# 05_LEDs.net
KiCad netlist of a schematic drawn in Altium Designer
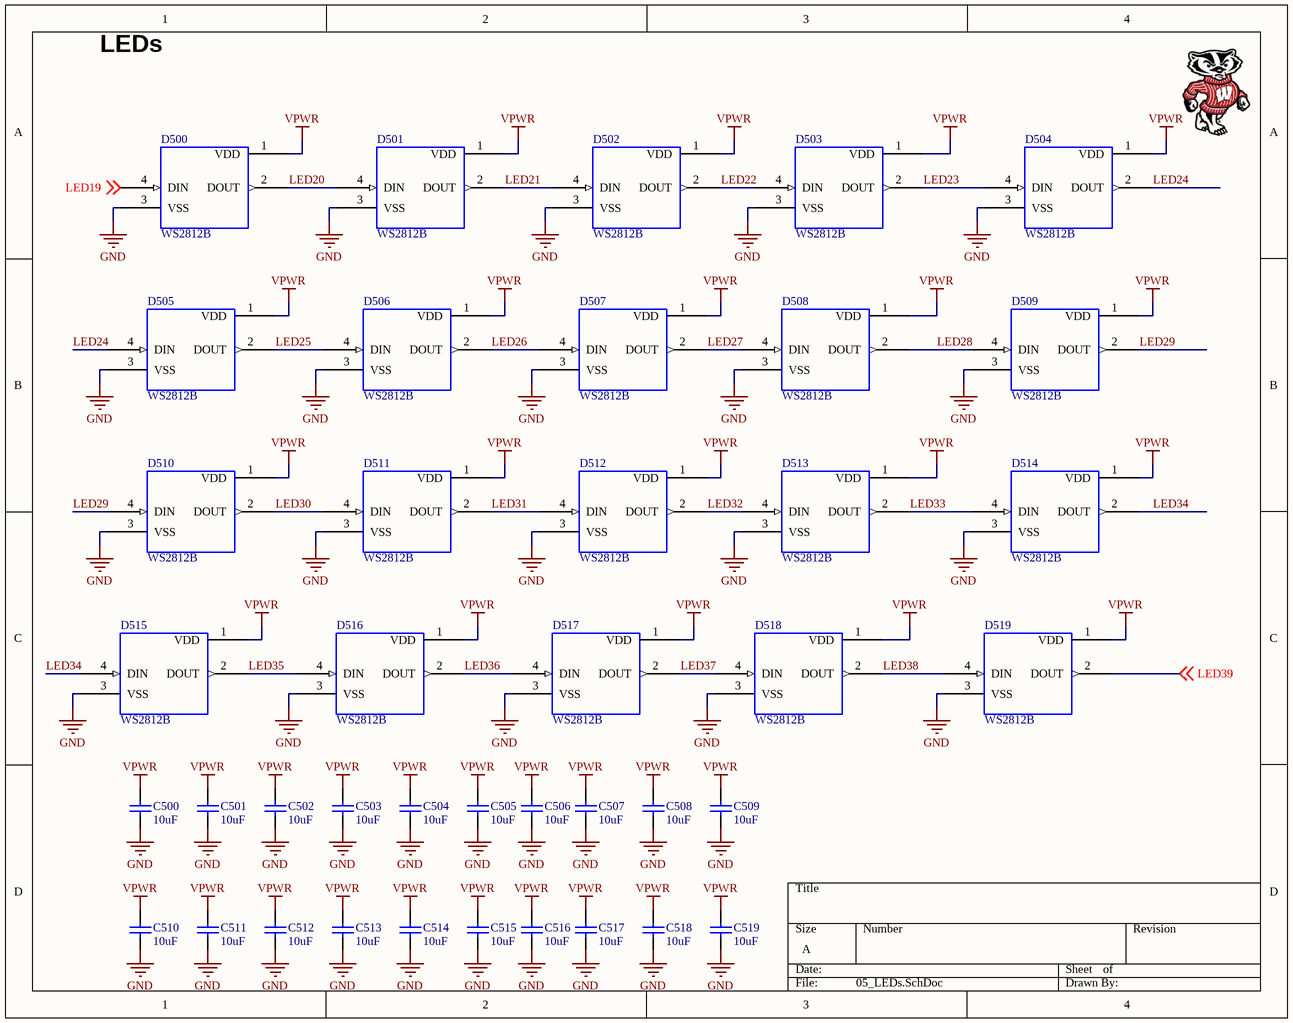
[diagram p0: 05_LEDs.SchDoc]

(export (version "E")
  (design (tool "Eeschema 10.0.6"))
  (components
    (comp (ref "C500")
      (value "10uF")
      (footprint "CAP_0805")
      (description "CAP CER 10UF 16V X7R 0805")
      (fields
        (field (name "MANUFACTURER") "Samsung")
        (field (name "MANUFACTURER PART NUMBER") "CL21A106KPCLQNC")
        (field (name "CAPACITANCE") "10uF")
      )
      (libsource (lib "ece315-2018-fall") (part "CAP_0805_U_010.00"))
    )
    (comp (ref "C501")
      (value "10uF")
      (footprint "CAP_0805")
      (description "CAP CER 10UF 16V X7R 0805")
      (fields
        (field (name "MANUFACTURER") "Samsung")
        (field (name "MANUFACTURER PART NUMBER") "CL21A106KPCLQNC")
        (field (name "CAPACITANCE") "10uF")
      )
      (libsource (lib "ece315-2018-fall") (part "CAP_0805_U_010.00"))
    )
    (comp (ref "C502")
      (value "10uF")
      (footprint "CAP_0805")
      (description "CAP CER 10UF 16V X7R 0805")
      (fields
        (field (name "MANUFACTURER") "Samsung")
        (field (name "MANUFACTURER PART NUMBER") "CL21A106KPCLQNC")
        (field (name "CAPACITANCE") "10uF")
      )
      (libsource (lib "ece315-2018-fall") (part "CAP_0805_U_010.00"))
    )
    (comp (ref "C503")
      (value "10uF")
      (footprint "CAP_0805")
      (description "CAP CER 10UF 16V X7R 0805")
      (fields
        (field (name "MANUFACTURER") "Samsung")
        (field (name "MANUFACTURER PART NUMBER") "CL21A106KPCLQNC")
        (field (name "CAPACITANCE") "10uF")
      )
      (libsource (lib "ece315-2018-fall") (part "CAP_0805_U_010.00"))
    )
    (comp (ref "C504")
      (value "10uF")
      (footprint "CAP_0805")
      (description "CAP CER 10UF 16V X7R 0805")
      (fields
        (field (name "MANUFACTURER") "Samsung")
        (field (name "MANUFACTURER PART NUMBER") "CL21A106KPCLQNC")
        (field (name "CAPACITANCE") "10uF")
      )
      (libsource (lib "ece315-2018-fall") (part "CAP_0805_U_010.00"))
    )
    (comp (ref "C505")
      (value "10uF")
      (footprint "CAP_0805")
      (description "CAP CER 10UF 16V X7R 0805")
      (fields
        (field (name "MANUFACTURER") "Samsung")
        (field (name "MANUFACTURER PART NUMBER") "CL21A106KPCLQNC")
        (field (name "CAPACITANCE") "10uF")
      )
      (libsource (lib "ece315-2018-fall") (part "CAP_0805_U_010.00"))
    )
    (comp (ref "C506")
      (value "10uF")
      (footprint "CAP_0805")
      (description "CAP CER 10UF 16V X7R 0805")
      (fields
        (field (name "MANUFACTURER") "Samsung")
        (field (name "MANUFACTURER PART NUMBER") "CL21A106KPCLQNC")
        (field (name "CAPACITANCE") "10uF")
      )
      (libsource (lib "ece315-2018-fall") (part "CAP_0805_U_010.00"))
    )
    (comp (ref "C507")
      (value "10uF")
      (footprint "CAP_0805")
      (description "CAP CER 10UF 16V X7R 0805")
      (fields
        (field (name "MANUFACTURER") "Samsung")
        (field (name "MANUFACTURER PART NUMBER") "CL21A106KPCLQNC")
        (field (name "CAPACITANCE") "10uF")
      )
      (libsource (lib "ece315-2018-fall") (part "CAP_0805_U_010.00"))
    )
    (comp (ref "C508")
      (value "10uF")
      (footprint "CAP_0805")
      (description "CAP CER 10UF 16V X7R 0805")
      (fields
        (field (name "MANUFACTURER") "Samsung")
        (field (name "MANUFACTURER PART NUMBER") "CL21A106KPCLQNC")
        (field (name "CAPACITANCE") "10uF")
      )
      (libsource (lib "ece315-2018-fall") (part "CAP_0805_U_010.00"))
    )
    (comp (ref "C509")
      (value "10uF")
      (footprint "CAP_0805")
      (description "CAP CER 10UF 16V X7R 0805")
      (fields
        (field (name "MANUFACTURER") "Samsung")
        (field (name "MANUFACTURER PART NUMBER") "CL21A106KPCLQNC")
        (field (name "CAPACITANCE") "10uF")
      )
      (libsource (lib "ece315-2018-fall") (part "CAP_0805_U_010.00"))
    )
    (comp (ref "C510")
      (value "10uF")
      (footprint "CAP_0805")
      (description "CAP CER 10UF 16V X7R 0805")
      (fields
        (field (name "MANUFACTURER") "Samsung")
        (field (name "MANUFACTURER PART NUMBER") "CL21A106KPCLQNC")
        (field (name "CAPACITANCE") "10uF")
      )
      (libsource (lib "ece315-2018-fall") (part "CAP_0805_U_010.00"))
    )
    (comp (ref "C511")
      (value "10uF")
      (footprint "CAP_0805")
      (description "CAP CER 10UF 16V X7R 0805")
      (fields
        (field (name "MANUFACTURER") "Samsung")
        (field (name "MANUFACTURER PART NUMBER") "CL21A106KPCLQNC")
        (field (name "CAPACITANCE") "10uF")
      )
      (libsource (lib "ece315-2018-fall") (part "CAP_0805_U_010.00"))
    )
    (comp (ref "C512")
      (value "10uF")
      (footprint "CAP_0805")
      (description "CAP CER 10UF 16V X7R 0805")
      (fields
        (field (name "MANUFACTURER") "Samsung")
        (field (name "MANUFACTURER PART NUMBER") "CL21A106KPCLQNC")
        (field (name "CAPACITANCE") "10uF")
      )
      (libsource (lib "ece315-2018-fall") (part "CAP_0805_U_010.00"))
    )
    (comp (ref "C513")
      (value "10uF")
      (footprint "CAP_0805")
      (description "CAP CER 10UF 16V X7R 0805")
      (fields
        (field (name "MANUFACTURER") "Samsung")
        (field (name "MANUFACTURER PART NUMBER") "CL21A106KPCLQNC")
        (field (name "CAPACITANCE") "10uF")
      )
      (libsource (lib "ece315-2018-fall") (part "CAP_0805_U_010.00"))
    )
    (comp (ref "C514")
      (value "10uF")
      (footprint "CAP_0805")
      (description "CAP CER 10UF 16V X7R 0805")
      (fields
        (field (name "MANUFACTURER") "Samsung")
        (field (name "MANUFACTURER PART NUMBER") "CL21A106KPCLQNC")
        (field (name "CAPACITANCE") "10uF")
      )
      (libsource (lib "ece315-2018-fall") (part "CAP_0805_U_010.00"))
    )
    (comp (ref "C515")
      (value "10uF")
      (footprint "CAP_0805")
      (description "CAP CER 10UF 16V X7R 0805")
      (fields
        (field (name "MANUFACTURER") "Samsung")
        (field (name "MANUFACTURER PART NUMBER") "CL21A106KPCLQNC")
        (field (name "CAPACITANCE") "10uF")
      )
      (libsource (lib "ece315-2018-fall") (part "CAP_0805_U_010.00"))
    )
    (comp (ref "C516")
      (value "10uF")
      (footprint "CAP_0805")
      (description "CAP CER 10UF 16V X7R 0805")
      (fields
        (field (name "MANUFACTURER") "Samsung")
        (field (name "MANUFACTURER PART NUMBER") "CL21A106KPCLQNC")
        (field (name "CAPACITANCE") "10uF")
      )
      (libsource (lib "ece315-2018-fall") (part "CAP_0805_U_010.00"))
    )
    (comp (ref "C517")
      (value "10uF")
      (footprint "CAP_0805")
      (description "CAP CER 10UF 16V X7R 0805")
      (fields
        (field (name "MANUFACTURER") "Samsung")
        (field (name "MANUFACTURER PART NUMBER") "CL21A106KPCLQNC")
        (field (name "CAPACITANCE") "10uF")
      )
      (libsource (lib "ece315-2018-fall") (part "CAP_0805_U_010.00"))
    )
    (comp (ref "C518")
      (value "10uF")
      (footprint "CAP_0805")
      (description "CAP CER 10UF 16V X7R 0805")
      (fields
        (field (name "MANUFACTURER") "Samsung")
        (field (name "MANUFACTURER PART NUMBER") "CL21A106KPCLQNC")
        (field (name "CAPACITANCE") "10uF")
      )
      (libsource (lib "ece315-2018-fall") (part "CAP_0805_U_010.00"))
    )
    (comp (ref "C519")
      (value "10uF")
      (footprint "CAP_0805")
      (description "CAP CER 10UF 16V X7R 0805")
      (fields
        (field (name "MANUFACTURER") "Samsung")
        (field (name "MANUFACTURER PART NUMBER") "CL21A106KPCLQNC")
        (field (name "CAPACITANCE") "10uF")
      )
      (libsource (lib "ece315-2018-fall") (part "CAP_0805_U_010.00"))
    )
    (comp (ref "D500")
      (value "WS2812B")
      (footprint "WS2812B")
      (description "LED RGB WS2812B")
      (fields (field (name "MANUFACTURER PART NUMBER") "EBAY"))
      (libsource (lib "LEDs") (part "WS2812B"))
    )
    (comp (ref "D501")
      (value "WS2812B")
      (footprint "WS2812B")
      (description "LED RGB WS2812B")
      (fields (field (name "MANUFACTURER PART NUMBER") "EBAY"))
      (libsource (lib "LEDs") (part "WS2812B"))
    )
    (comp (ref "D502")
      (value "WS2812B")
      (footprint "WS2812B")
      (description "LED RGB WS2812B")
      (fields (field (name "MANUFACTURER PART NUMBER") "EBAY"))
      (libsource (lib "LEDs") (part "WS2812B"))
    )
    (comp (ref "D503")
      (value "WS2812B")
      (footprint "WS2812B")
      (description "LED RGB WS2812B")
      (fields (field (name "MANUFACTURER PART NUMBER") "EBAY"))
      (libsource (lib "LEDs") (part "WS2812B"))
    )
    (comp (ref "D504")
      (value "WS2812B")
      (footprint "WS2812B")
      (description "LED RGB WS2812B")
      (fields (field (name "MANUFACTURER PART NUMBER") "EBAY"))
      (libsource (lib "LEDs") (part "WS2812B"))
    )
    (comp (ref "D505")
      (value "WS2812B")
      (footprint "WS2812B")
      (description "LED RGB WS2812B")
      (fields (field (name "MANUFACTURER PART NUMBER") "EBAY"))
      (libsource (lib "LEDs") (part "WS2812B"))
    )
    (comp (ref "D506")
      (value "WS2812B")
      (footprint "WS2812B")
      (description "LED RGB WS2812B")
      (fields (field (name "MANUFACTURER PART NUMBER") "EBAY"))
      (libsource (lib "LEDs") (part "WS2812B"))
    )
    (comp (ref "D507")
      (value "WS2812B")
      (footprint "WS2812B")
      (description "LED RGB WS2812B")
      (fields (field (name "MANUFACTURER PART NUMBER") "EBAY"))
      (libsource (lib "LEDs") (part "WS2812B"))
    )
    (comp (ref "D508")
      (value "WS2812B")
      (footprint "WS2812B")
      (description "LED RGB WS2812B")
      (fields (field (name "MANUFACTURER PART NUMBER") "EBAY"))
      (libsource (lib "LEDs") (part "WS2812B"))
    )
    (comp (ref "D509")
      (value "WS2812B")
      (footprint "WS2812B")
      (description "LED RGB WS2812B")
      (fields (field (name "MANUFACTURER PART NUMBER") "EBAY"))
      (libsource (lib "LEDs") (part "WS2812B"))
    )
    (comp (ref "D510")
      (value "WS2812B")
      (footprint "WS2812B")
      (description "LED RGB WS2812B")
      (fields (field (name "MANUFACTURER PART NUMBER") "EBAY"))
      (libsource (lib "LEDs") (part "WS2812B"))
    )
    (comp (ref "D511")
      (value "WS2812B")
      (footprint "WS2812B")
      (description "LED RGB WS2812B")
      (fields (field (name "MANUFACTURER PART NUMBER") "EBAY"))
      (libsource (lib "LEDs") (part "WS2812B"))
    )
    (comp (ref "D512")
      (value "WS2812B")
      (footprint "WS2812B")
      (description "LED RGB WS2812B")
      (fields (field (name "MANUFACTURER PART NUMBER") "EBAY"))
      (libsource (lib "LEDs") (part "WS2812B"))
    )
    (comp (ref "D513")
      (value "WS2812B")
      (footprint "WS2812B")
      (description "LED RGB WS2812B")
      (fields (field (name "MANUFACTURER PART NUMBER") "EBAY"))
      (libsource (lib "LEDs") (part "WS2812B"))
    )
    (comp (ref "D514")
      (value "WS2812B")
      (footprint "WS2812B")
      (description "LED RGB WS2812B")
      (fields (field (name "MANUFACTURER PART NUMBER") "EBAY"))
      (libsource (lib "LEDs") (part "WS2812B"))
    )
    (comp (ref "D515")
      (value "WS2812B")
      (footprint "WS2812B")
      (description "LED RGB WS2812B")
      (fields (field (name "MANUFACTURER PART NUMBER") "EBAY"))
      (libsource (lib "LEDs") (part "WS2812B"))
    )
    (comp (ref "D516")
      (value "WS2812B")
      (footprint "WS2812B")
      (description "LED RGB WS2812B")
      (fields (field (name "MANUFACTURER PART NUMBER") "EBAY"))
      (libsource (lib "LEDs") (part "WS2812B"))
    )
    (comp (ref "D517")
      (value "WS2812B")
      (footprint "WS2812B")
      (description "LED RGB WS2812B")
      (fields (field (name "MANUFACTURER PART NUMBER") "EBAY"))
      (libsource (lib "LEDs") (part "WS2812B"))
    )
    (comp (ref "D518")
      (value "WS2812B")
      (footprint "WS2812B")
      (description "LED RGB WS2812B")
      (fields (field (name "MANUFACTURER PART NUMBER") "EBAY"))
      (libsource (lib "LEDs") (part "WS2812B"))
    )
    (comp (ref "D519")
      (value "WS2812B")
      (footprint "WS2812B")
      (description "LED RGB WS2812B")
      (fields (field (name "MANUFACTURER PART NUMBER") "EBAY"))
      (libsource (lib "LEDs") (part "WS2812B"))
    )
  )
  (nets
    (net (code "1") (name "/LED20") (class "Default")
      (node (ref "D500") (pin "2") (pinfunction "DOUT_2") (pintype "output"))
      (node (ref "D501") (pin "4") (pinfunction "DIN_4") (pintype "input"))
    )
    (net (code "2") (name "/LED21") (class "Default")
      (node (ref "D501") (pin "2") (pinfunction "DOUT_2") (pintype "output"))
      (node (ref "D502") (pin "4") (pinfunction "DIN_4") (pintype "input"))
    )
    (net (code "3") (name "/LED22") (class "Default")
      (node (ref "D502") (pin "2") (pinfunction "DOUT_2") (pintype "output"))
      (node (ref "D503") (pin "4") (pinfunction "DIN_4") (pintype "input"))
    )
    (net (code "4") (name "/LED23") (class "Default")
      (node (ref "D503") (pin "2") (pinfunction "DOUT_2") (pintype "output"))
      (node (ref "D504") (pin "4") (pinfunction "DIN_4") (pintype "input"))
    )
    (net (code "5") (name "/LED24") (class "Default")
      (node (ref "D504") (pin "2") (pinfunction "DOUT_2") (pintype "output"))
      (node (ref "D505") (pin "4") (pinfunction "DIN_4") (pintype "input"))
    )
    (net (code "6") (name "/LED25") (class "Default")
      (node (ref "D505") (pin "2") (pinfunction "DOUT_2") (pintype "output"))
      (node (ref "D506") (pin "4") (pinfunction "DIN_4") (pintype "input"))
    )
    (net (code "7") (name "/LED26") (class "Default")
      (node (ref "D506") (pin "2") (pinfunction "DOUT_2") (pintype "output"))
      (node (ref "D507") (pin "4") (pinfunction "DIN_4") (pintype "input"))
    )
    (net (code "8") (name "/LED27") (class "Default")
      (node (ref "D507") (pin "2") (pinfunction "DOUT_2") (pintype "output"))
      (node (ref "D508") (pin "4") (pinfunction "DIN_4") (pintype "input"))
    )
    (net (code "9") (name "/LED28") (class "Default")
      (node (ref "D508") (pin "2") (pinfunction "DOUT_2") (pintype "output"))
      (node (ref "D509") (pin "4") (pinfunction "DIN_4") (pintype "input"))
    )
    (net (code "10") (name "/LED29") (class "Default")
      (node (ref "D509") (pin "2") (pinfunction "DOUT_2") (pintype "output"))
      (node (ref "D510") (pin "4") (pinfunction "DIN_4") (pintype "input"))
    )
    (net (code "11") (name "/LED30") (class "Default")
      (node (ref "D510") (pin "2") (pinfunction "DOUT_2") (pintype "output"))
      (node (ref "D511") (pin "4") (pinfunction "DIN_4") (pintype "input"))
    )
    (net (code "12") (name "/LED31") (class "Default")
      (node (ref "D511") (pin "2") (pinfunction "DOUT_2") (pintype "output"))
      (node (ref "D512") (pin "4") (pinfunction "DIN_4") (pintype "input"))
    )
    (net (code "13") (name "/LED32") (class "Default")
      (node (ref "D512") (pin "2") (pinfunction "DOUT_2") (pintype "output"))
      (node (ref "D513") (pin "4") (pinfunction "DIN_4") (pintype "input"))
    )
    (net (code "14") (name "/LED33") (class "Default")
      (node (ref "D513") (pin "2") (pinfunction "DOUT_2") (pintype "output"))
      (node (ref "D514") (pin "4") (pinfunction "DIN_4") (pintype "input"))
    )
    (net (code "15") (name "/LED34") (class "Default")
      (node (ref "D514") (pin "2") (pinfunction "DOUT_2") (pintype "output"))
      (node (ref "D515") (pin "4") (pinfunction "DIN_4") (pintype "input"))
    )
    (net (code "16") (name "/LED35") (class "Default")
      (node (ref "D515") (pin "2") (pinfunction "DOUT_2") (pintype "output"))
      (node (ref "D516") (pin "4") (pinfunction "DIN_4") (pintype "input"))
    )
    (net (code "17") (name "/LED36") (class "Default")
      (node (ref "D516") (pin "2") (pinfunction "DOUT_2") (pintype "output"))
      (node (ref "D517") (pin "4") (pinfunction "DIN_4") (pintype "input"))
    )
    (net (code "18") (name "/LED37") (class "Default")
      (node (ref "D517") (pin "2") (pinfunction "DOUT_2") (pintype "output"))
      (node (ref "D518") (pin "4") (pinfunction "DIN_4") (pintype "input"))
    )
    (net (code "19") (name "/LED38") (class "Default")
      (node (ref "D518") (pin "2") (pinfunction "DOUT_2") (pintype "output"))
      (node (ref "D519") (pin "4") (pinfunction "DIN_4") (pintype "input"))
    )
    (net (code "20") (name "GND") (class "Default")
      (node (ref "C500") (pin "1") (pinfunction "1_1") (pintype "passive"))
      (node (ref "C501") (pin "1") (pinfunction "1_1") (pintype "passive"))
      (node (ref "C502") (pin "1") (pinfunction "1_1") (pintype "passive"))
      (node (ref "C503") (pin "1") (pinfunction "1_1") (pintype "passive"))
      (node (ref "C504") (pin "1") (pinfunction "1_1") (pintype "passive"))
      (node (ref "C505") (pin "1") (pinfunction "1_1") (pintype "passive"))
      (node (ref "C506") (pin "1") (pinfunction "1_1") (pintype "passive"))
      (node (ref "C507") (pin "1") (pinfunction "1_1") (pintype "passive"))
      (node (ref "C508") (pin "1") (pinfunction "1_1") (pintype "passive"))
      (node (ref "C509") (pin "1") (pinfunction "1_1") (pintype "passive"))
      (node (ref "C510") (pin "1") (pinfunction "1_1") (pintype "passive"))
      (node (ref "C511") (pin "1") (pinfunction "1_1") (pintype "passive"))
      (node (ref "C512") (pin "1") (pinfunction "1_1") (pintype "passive"))
      (node (ref "C513") (pin "1") (pinfunction "1_1") (pintype "passive"))
      (node (ref "C514") (pin "1") (pinfunction "1_1") (pintype "passive"))
      (node (ref "C515") (pin "1") (pinfunction "1_1") (pintype "passive"))
      (node (ref "C516") (pin "1") (pinfunction "1_1") (pintype "passive"))
      (node (ref "C517") (pin "1") (pinfunction "1_1") (pintype "passive"))
      (node (ref "C518") (pin "1") (pinfunction "1_1") (pintype "passive"))
      (node (ref "C519") (pin "1") (pinfunction "1_1") (pintype "passive"))
      (node (ref "D500") (pin "3") (pinfunction "VSS_3") (pintype "power_in"))
      (node (ref "D501") (pin "3") (pinfunction "VSS_3") (pintype "power_in"))
      (node (ref "D502") (pin "3") (pinfunction "VSS_3") (pintype "power_in"))
      (node (ref "D503") (pin "3") (pinfunction "VSS_3") (pintype "power_in"))
      (node (ref "D504") (pin "3") (pinfunction "VSS_3") (pintype "power_in"))
      (node (ref "D505") (pin "3") (pinfunction "VSS_3") (pintype "power_in"))
      (node (ref "D506") (pin "3") (pinfunction "VSS_3") (pintype "power_in"))
      (node (ref "D507") (pin "3") (pinfunction "VSS_3") (pintype "power_in"))
      (node (ref "D508") (pin "3") (pinfunction "VSS_3") (pintype "power_in"))
      (node (ref "D509") (pin "3") (pinfunction "VSS_3") (pintype "power_in"))
      (node (ref "D510") (pin "3") (pinfunction "VSS_3") (pintype "power_in"))
      (node (ref "D511") (pin "3") (pinfunction "VSS_3") (pintype "power_in"))
      (node (ref "D512") (pin "3") (pinfunction "VSS_3") (pintype "power_in"))
      (node (ref "D513") (pin "3") (pinfunction "VSS_3") (pintype "power_in"))
      (node (ref "D514") (pin "3") (pinfunction "VSS_3") (pintype "power_in"))
      (node (ref "D515") (pin "3") (pinfunction "VSS_3") (pintype "power_in"))
      (node (ref "D516") (pin "3") (pinfunction "VSS_3") (pintype "power_in"))
      (node (ref "D517") (pin "3") (pinfunction "VSS_3") (pintype "power_in"))
      (node (ref "D518") (pin "3") (pinfunction "VSS_3") (pintype "power_in"))
      (node (ref "D519") (pin "3") (pinfunction "VSS_3") (pintype "power_in"))
    )
    (net (code "21") (name "LED19") (class "Default")
      (node (ref "D500") (pin "4") (pinfunction "DIN_4") (pintype "input"))
    )
    (net (code "22") (name "LED39") (class "Default")
      (node (ref "D519") (pin "2") (pinfunction "DOUT_2") (pintype "output"))
    )
    (net (code "23") (name "VPWR") (class "Default")
      (node (ref "C500") (pin "2") (pinfunction "2_2") (pintype "passive"))
      (node (ref "C501") (pin "2") (pinfunction "2_2") (pintype "passive"))
      (node (ref "C502") (pin "2") (pinfunction "2_2") (pintype "passive"))
      (node (ref "C503") (pin "2") (pinfunction "2_2") (pintype "passive"))
      (node (ref "C504") (pin "2") (pinfunction "2_2") (pintype "passive"))
      (node (ref "C505") (pin "2") (pinfunction "2_2") (pintype "passive"))
      (node (ref "C506") (pin "2") (pinfunction "2_2") (pintype "passive"))
      (node (ref "C507") (pin "2") (pinfunction "2_2") (pintype "passive"))
      (node (ref "C508") (pin "2") (pinfunction "2_2") (pintype "passive"))
      (node (ref "C509") (pin "2") (pinfunction "2_2") (pintype "passive"))
      (node (ref "C510") (pin "2") (pinfunction "2_2") (pintype "passive"))
      (node (ref "C511") (pin "2") (pinfunction "2_2") (pintype "passive"))
      (node (ref "C512") (pin "2") (pinfunction "2_2") (pintype "passive"))
      (node (ref "C513") (pin "2") (pinfunction "2_2") (pintype "passive"))
      (node (ref "C514") (pin "2") (pinfunction "2_2") (pintype "passive"))
      (node (ref "C515") (pin "2") (pinfunction "2_2") (pintype "passive"))
      (node (ref "C516") (pin "2") (pinfunction "2_2") (pintype "passive"))
      (node (ref "C517") (pin "2") (pinfunction "2_2") (pintype "passive"))
      (node (ref "C518") (pin "2") (pinfunction "2_2") (pintype "passive"))
      (node (ref "C519") (pin "2") (pinfunction "2_2") (pintype "passive"))
      (node (ref "D500") (pin "1") (pinfunction "VDD_1") (pintype "power_in"))
      (node (ref "D501") (pin "1") (pinfunction "VDD_1") (pintype "power_in"))
      (node (ref "D502") (pin "1") (pinfunction "VDD_1") (pintype "power_in"))
      (node (ref "D503") (pin "1") (pinfunction "VDD_1") (pintype "power_in"))
      (node (ref "D504") (pin "1") (pinfunction "VDD_1") (pintype "power_in"))
      (node (ref "D505") (pin "1") (pinfunction "VDD_1") (pintype "power_in"))
      (node (ref "D506") (pin "1") (pinfunction "VDD_1") (pintype "power_in"))
      (node (ref "D507") (pin "1") (pinfunction "VDD_1") (pintype "power_in"))
      (node (ref "D508") (pin "1") (pinfunction "VDD_1") (pintype "power_in"))
      (node (ref "D509") (pin "1") (pinfunction "VDD_1") (pintype "power_in"))
      (node (ref "D510") (pin "1") (pinfunction "VDD_1") (pintype "power_in"))
      (node (ref "D511") (pin "1") (pinfunction "VDD_1") (pintype "power_in"))
      (node (ref "D512") (pin "1") (pinfunction "VDD_1") (pintype "power_in"))
      (node (ref "D513") (pin "1") (pinfunction "VDD_1") (pintype "power_in"))
      (node (ref "D514") (pin "1") (pinfunction "VDD_1") (pintype "power_in"))
      (node (ref "D515") (pin "1") (pinfunction "VDD_1") (pintype "power_in"))
      (node (ref "D516") (pin "1") (pinfunction "VDD_1") (pintype "power_in"))
      (node (ref "D517") (pin "1") (pinfunction "VDD_1") (pintype "power_in"))
      (node (ref "D518") (pin "1") (pinfunction "VDD_1") (pintype "power_in"))
      (node (ref "D519") (pin "1") (pinfunction "VDD_1") (pintype "power_in"))
    )
  )
)
